# ai_blinkle_16.net
KiCad netlist of a schematic drawn in EAGLE
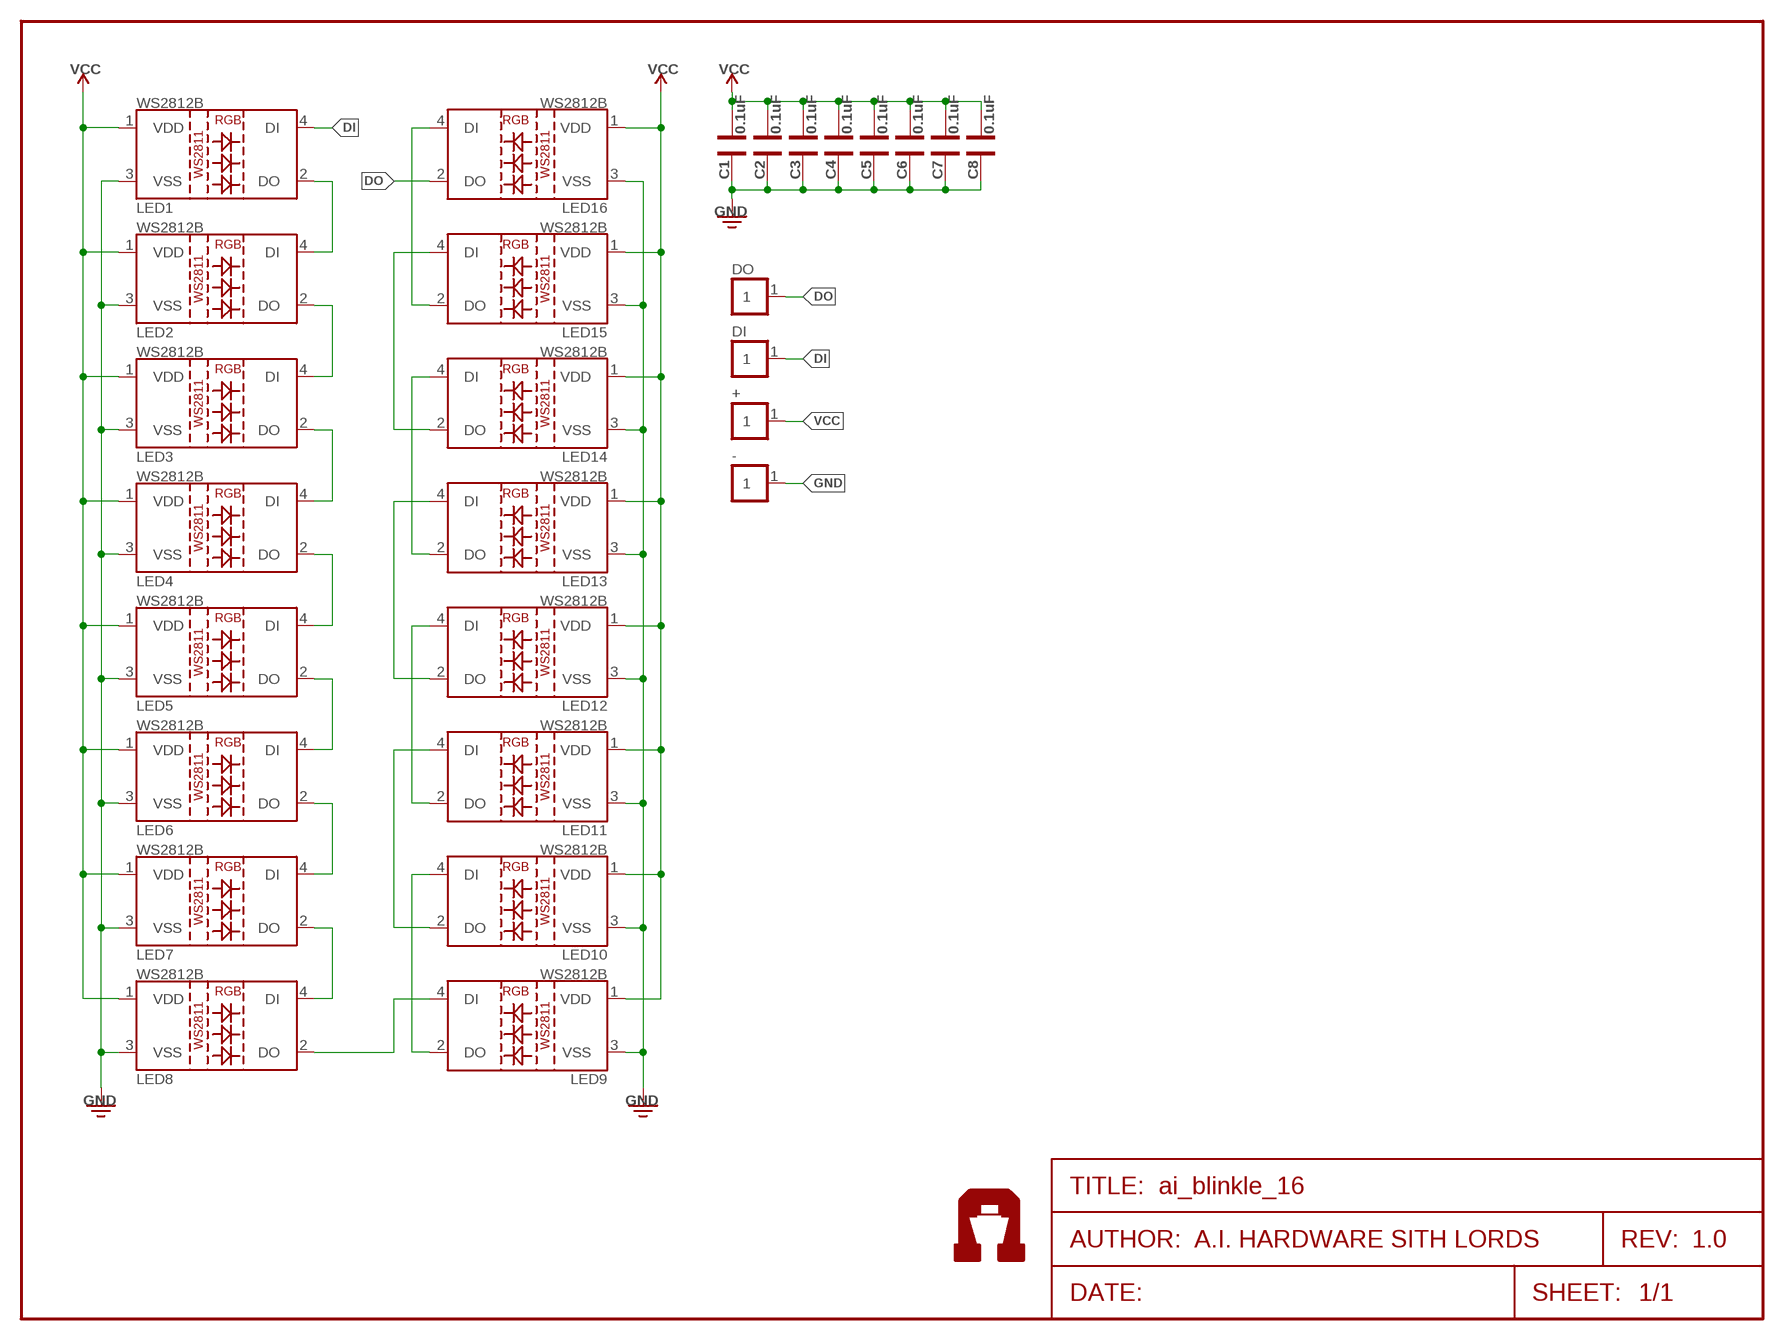
[diagram p0: schematic, sheet 1]

(export (version "E")
  (design (tool "Eeschema 10.0.6"))
  (components
    (comp (ref "+")
      (value "1X01-SM")
      (footprint "eagle-import:1X01-SM")
      (libsource (lib "eagle-import") (part "1X01-SM"))
    )
    (comp (ref "-")
      (value "1X01-SM")
      (footprint "eagle-import:1X01-SM")
      (libsource (lib "eagle-import") (part "1X01-SM"))
    )
    (comp (ref "C1")
      (value "0.1uF")
      (footprint "eagle-import:CAP-0402")
      (libsource (lib "eagle-import") (part "CAP0402"))
    )
    (comp (ref "C2")
      (value "0.1uF")
      (footprint "eagle-import:CAP-0402")
      (libsource (lib "eagle-import") (part "CAP0402"))
    )
    (comp (ref "C3")
      (value "0.1uF")
      (footprint "eagle-import:CAP-0402")
      (libsource (lib "eagle-import") (part "CAP0402"))
    )
    (comp (ref "C4")
      (value "0.1uF")
      (footprint "eagle-import:CAP-0402")
      (libsource (lib "eagle-import") (part "CAP0402"))
    )
    (comp (ref "C5")
      (value "0.1uF")
      (footprint "eagle-import:CAP-0402")
      (libsource (lib "eagle-import") (part "CAP0402"))
    )
    (comp (ref "C6")
      (value "0.1uF")
      (footprint "eagle-import:CAP-0402")
      (libsource (lib "eagle-import") (part "CAP0402"))
    )
    (comp (ref "C7")
      (value "0.1uF")
      (footprint "eagle-import:CAP-0402")
      (libsource (lib "eagle-import") (part "CAP0402"))
    )
    (comp (ref "C8")
      (value "0.1uF")
      (footprint "eagle-import:CAP-0402")
      (libsource (lib "eagle-import") (part "CAP0402"))
    )
    (comp (ref "DI")
      (value "1X01-SM")
      (footprint "eagle-import:1X01-SM")
      (libsource (lib "eagle-import") (part "1X01-SM"))
    )
    (comp (ref "DO")
      (value "1X01-SM")
      (footprint "eagle-import:1X01-SM")
      (libsource (lib "eagle-import") (part "1X01-SM"))
    )
    (comp (ref "LED1")
      (value "LED-WS2812B-SM")
      (footprint "eagle-import:LED-WS2812B-SM")
      (libsource (lib "eagle-import") (part "LED-WS2812B-SM"))
    )
    (comp (ref "LED2")
      (value "LED-WS2812B-SM")
      (footprint "eagle-import:LED-WS2812B-SM")
      (libsource (lib "eagle-import") (part "LED-WS2812B-SM"))
    )
    (comp (ref "LED3")
      (value "LED-WS2812B-SM")
      (footprint "eagle-import:LED-WS2812B-SM")
      (libsource (lib "eagle-import") (part "LED-WS2812B-SM"))
    )
    (comp (ref "LED4")
      (value "LED-WS2812B-SM")
      (footprint "eagle-import:LED-WS2812B-SM")
      (libsource (lib "eagle-import") (part "LED-WS2812B-SM"))
    )
    (comp (ref "LED5")
      (value "LED-WS2812B-SM")
      (footprint "eagle-import:LED-WS2812B-SM")
      (libsource (lib "eagle-import") (part "LED-WS2812B-SM"))
    )
    (comp (ref "LED6")
      (value "LED-WS2812B-SM")
      (footprint "eagle-import:LED-WS2812B-SM")
      (libsource (lib "eagle-import") (part "LED-WS2812B-SM"))
    )
    (comp (ref "LED7")
      (value "LED-WS2812B-SM")
      (footprint "eagle-import:LED-WS2812B-SM")
      (libsource (lib "eagle-import") (part "LED-WS2812B-SM"))
    )
    (comp (ref "LED8")
      (value "LED-WS2812B-SM")
      (footprint "eagle-import:LED-WS2812B-SM")
      (libsource (lib "eagle-import") (part "LED-WS2812B-SM"))
    )
    (comp (ref "LED9")
      (value "LED-WS2812B-SM")
      (footprint "eagle-import:LED-WS2812B-SM")
      (libsource (lib "eagle-import") (part "LED-WS2812B-SM"))
    )
    (comp (ref "LED10")
      (value "LED-WS2812B-SM")
      (footprint "eagle-import:LED-WS2812B-SM")
      (libsource (lib "eagle-import") (part "LED-WS2812B-SM"))
    )
    (comp (ref "LED11")
      (value "LED-WS2812B-SM")
      (footprint "eagle-import:LED-WS2812B-SM")
      (libsource (lib "eagle-import") (part "LED-WS2812B-SM"))
    )
    (comp (ref "LED12")
      (value "LED-WS2812B-SM")
      (footprint "eagle-import:LED-WS2812B-SM")
      (libsource (lib "eagle-import") (part "LED-WS2812B-SM"))
    )
    (comp (ref "LED13")
      (value "LED-WS2812B-SM")
      (footprint "eagle-import:LED-WS2812B-SM")
      (libsource (lib "eagle-import") (part "LED-WS2812B-SM"))
    )
    (comp (ref "LED14")
      (value "LED-WS2812B-SM")
      (footprint "eagle-import:LED-WS2812B-SM")
      (libsource (lib "eagle-import") (part "LED-WS2812B-SM"))
    )
    (comp (ref "LED15")
      (value "LED-WS2812B-SM")
      (footprint "eagle-import:LED-WS2812B-SM")
      (libsource (lib "eagle-import") (part "LED-WS2812B-SM"))
    )
    (comp (ref "LED16")
      (value "LED-WS2812B-SM")
      (footprint "eagle-import:LED-WS2812B-SM")
      (libsource (lib "eagle-import") (part "LED-WS2812B-SM"))
    )
    (comp (ref "LOGO")
      (value "AI-LOGOXS")
      (footprint "eagle-import:AI-LOGO-XS")
      (libsource (lib "eagle-import") (part "AI-LOGOXS"))
    )
  )
  (nets
    (net (code "1") (name "DI") (class "Default")
      (node (ref "DI") (pin "1") (pinfunction "1_1") (pintype "bidirectional"))
      (node (ref "LED1") (pin "4") (pinfunction "DI_4") (pintype "bidirectional"))
    )
    (net (code "2") (name "DO") (class "Default")
      (node (ref "DO") (pin "1") (pinfunction "1_1") (pintype "bidirectional"))
      (node (ref "LED16") (pin "2") (pinfunction "DO_2") (pintype "bidirectional"))
    )
    (net (code "3") (name "GND") (class "Default")
      (node (ref "-") (pin "1") (pinfunction "1_1") (pintype "bidirectional"))
      (node (ref "C1") (pin "2") (pinfunction "2_2") (pintype "passive"))
      (node (ref "C2") (pin "2") (pinfunction "2_2") (pintype "passive"))
      (node (ref "C3") (pin "2") (pinfunction "2_2") (pintype "passive"))
      (node (ref "C4") (pin "2") (pinfunction "2_2") (pintype "passive"))
      (node (ref "C5") (pin "2") (pinfunction "2_2") (pintype "passive"))
      (node (ref "C6") (pin "2") (pinfunction "2_2") (pintype "passive"))
      (node (ref "C7") (pin "2") (pinfunction "2_2") (pintype "passive"))
      (node (ref "C8") (pin "2") (pinfunction "2_2") (pintype "passive"))
      (node (ref "LED1") (pin "3") (pinfunction "VSS_3") (pintype "bidirectional"))
      (node (ref "LED10") (pin "3") (pinfunction "VSS_3") (pintype "bidirectional"))
      (node (ref "LED11") (pin "3") (pinfunction "VSS_3") (pintype "bidirectional"))
      (node (ref "LED12") (pin "3") (pinfunction "VSS_3") (pintype "bidirectional"))
      (node (ref "LED13") (pin "3") (pinfunction "VSS_3") (pintype "bidirectional"))
      (node (ref "LED14") (pin "3") (pinfunction "VSS_3") (pintype "bidirectional"))
      (node (ref "LED15") (pin "3") (pinfunction "VSS_3") (pintype "bidirectional"))
      (node (ref "LED16") (pin "3") (pinfunction "VSS_3") (pintype "bidirectional"))
      (node (ref "LED2") (pin "3") (pinfunction "VSS_3") (pintype "bidirectional"))
      (node (ref "LED3") (pin "3") (pinfunction "VSS_3") (pintype "bidirectional"))
      (node (ref "LED4") (pin "3") (pinfunction "VSS_3") (pintype "bidirectional"))
      (node (ref "LED5") (pin "3") (pinfunction "VSS_3") (pintype "bidirectional"))
      (node (ref "LED6") (pin "3") (pinfunction "VSS_3") (pintype "bidirectional"))
      (node (ref "LED7") (pin "3") (pinfunction "VSS_3") (pintype "bidirectional"))
      (node (ref "LED8") (pin "3") (pinfunction "VSS_3") (pintype "bidirectional"))
      (node (ref "LED9") (pin "3") (pinfunction "VSS_3") (pintype "bidirectional"))
    )
    (net (code "4") (name "Net-(LED1-DO)") (class "Default")
      (node (ref "LED1") (pin "2") (pinfunction "DO_2") (pintype "bidirectional"))
      (node (ref "LED2") (pin "4") (pinfunction "DI_4") (pintype "bidirectional"))
    )
    (net (code "5") (name "Net-(LED2-DO)") (class "Default")
      (node (ref "LED2") (pin "2") (pinfunction "DO_2") (pintype "bidirectional"))
      (node (ref "LED3") (pin "4") (pinfunction "DI_4") (pintype "bidirectional"))
    )
    (net (code "6") (name "Net-(LED3-DO)") (class "Default")
      (node (ref "LED3") (pin "2") (pinfunction "DO_2") (pintype "bidirectional"))
      (node (ref "LED4") (pin "4") (pinfunction "DI_4") (pintype "bidirectional"))
    )
    (net (code "7") (name "Net-(LED4-DO)") (class "Default")
      (node (ref "LED4") (pin "2") (pinfunction "DO_2") (pintype "bidirectional"))
      (node (ref "LED5") (pin "4") (pinfunction "DI_4") (pintype "bidirectional"))
    )
    (net (code "8") (name "Net-(LED5-DO)") (class "Default")
      (node (ref "LED5") (pin "2") (pinfunction "DO_2") (pintype "bidirectional"))
      (node (ref "LED6") (pin "4") (pinfunction "DI_4") (pintype "bidirectional"))
    )
    (net (code "9") (name "Net-(LED6-DO)") (class "Default")
      (node (ref "LED6") (pin "2") (pinfunction "DO_2") (pintype "bidirectional"))
      (node (ref "LED7") (pin "4") (pinfunction "DI_4") (pintype "bidirectional"))
    )
    (net (code "10") (name "Net-(LED7-DO)") (class "Default")
      (node (ref "LED7") (pin "2") (pinfunction "DO_2") (pintype "bidirectional"))
      (node (ref "LED8") (pin "4") (pinfunction "DI_4") (pintype "bidirectional"))
    )
    (net (code "11") (name "Net-(LED8-DO)") (class "Default")
      (node (ref "LED8") (pin "2") (pinfunction "DO_2") (pintype "bidirectional"))
      (node (ref "LED9") (pin "4") (pinfunction "DI_4") (pintype "bidirectional"))
    )
    (net (code "12") (name "Net-(LED10-DI)") (class "Default")
      (node (ref "LED10") (pin "4") (pinfunction "DI_4") (pintype "bidirectional"))
      (node (ref "LED9") (pin "2") (pinfunction "DO_2") (pintype "bidirectional"))
    )
    (net (code "13") (name "Net-(LED10-DO)") (class "Default")
      (node (ref "LED10") (pin "2") (pinfunction "DO_2") (pintype "bidirectional"))
      (node (ref "LED11") (pin "4") (pinfunction "DI_4") (pintype "bidirectional"))
    )
    (net (code "14") (name "Net-(LED11-DO)") (class "Default")
      (node (ref "LED11") (pin "2") (pinfunction "DO_2") (pintype "bidirectional"))
      (node (ref "LED12") (pin "4") (pinfunction "DI_4") (pintype "bidirectional"))
    )
    (net (code "15") (name "Net-(LED12-DO)") (class "Default")
      (node (ref "LED12") (pin "2") (pinfunction "DO_2") (pintype "bidirectional"))
      (node (ref "LED13") (pin "4") (pinfunction "DI_4") (pintype "bidirectional"))
    )
    (net (code "16") (name "Net-(LED13-DO)") (class "Default")
      (node (ref "LED13") (pin "2") (pinfunction "DO_2") (pintype "bidirectional"))
      (node (ref "LED14") (pin "4") (pinfunction "DI_4") (pintype "bidirectional"))
    )
    (net (code "17") (name "Net-(LED14-DO)") (class "Default")
      (node (ref "LED14") (pin "2") (pinfunction "DO_2") (pintype "bidirectional"))
      (node (ref "LED15") (pin "4") (pinfunction "DI_4") (pintype "bidirectional"))
    )
    (net (code "18") (name "Net-(LED15-DO)") (class "Default")
      (node (ref "LED15") (pin "2") (pinfunction "DO_2") (pintype "bidirectional"))
      (node (ref "LED16") (pin "4") (pinfunction "DI_4") (pintype "bidirectional"))
    )
    (net (code "19") (name "VCC") (class "Default")
      (node (ref "+") (pin "1") (pinfunction "1_1") (pintype "bidirectional"))
      (node (ref "C1") (pin "1") (pinfunction "1_1") (pintype "passive"))
      (node (ref "C2") (pin "1") (pinfunction "1_1") (pintype "passive"))
      (node (ref "C3") (pin "1") (pinfunction "1_1") (pintype "passive"))
      (node (ref "C4") (pin "1") (pinfunction "1_1") (pintype "passive"))
      (node (ref "C5") (pin "1") (pinfunction "1_1") (pintype "passive"))
      (node (ref "C6") (pin "1") (pinfunction "1_1") (pintype "passive"))
      (node (ref "C7") (pin "1") (pinfunction "1_1") (pintype "passive"))
      (node (ref "C8") (pin "1") (pinfunction "1_1") (pintype "passive"))
      (node (ref "LED1") (pin "1") (pinfunction "VDD_1") (pintype "bidirectional"))
      (node (ref "LED10") (pin "1") (pinfunction "VDD_1") (pintype "bidirectional"))
      (node (ref "LED11") (pin "1") (pinfunction "VDD_1") (pintype "bidirectional"))
      (node (ref "LED12") (pin "1") (pinfunction "VDD_1") (pintype "bidirectional"))
      (node (ref "LED13") (pin "1") (pinfunction "VDD_1") (pintype "bidirectional"))
      (node (ref "LED14") (pin "1") (pinfunction "VDD_1") (pintype "bidirectional"))
      (node (ref "LED15") (pin "1") (pinfunction "VDD_1") (pintype "bidirectional"))
      (node (ref "LED16") (pin "1") (pinfunction "VDD_1") (pintype "bidirectional"))
      (node (ref "LED2") (pin "1") (pinfunction "VDD_1") (pintype "bidirectional"))
      (node (ref "LED3") (pin "1") (pinfunction "VDD_1") (pintype "bidirectional"))
      (node (ref "LED4") (pin "1") (pinfunction "VDD_1") (pintype "bidirectional"))
      (node (ref "LED5") (pin "1") (pinfunction "VDD_1") (pintype "bidirectional"))
      (node (ref "LED6") (pin "1") (pinfunction "VDD_1") (pintype "bidirectional"))
      (node (ref "LED7") (pin "1") (pinfunction "VDD_1") (pintype "bidirectional"))
      (node (ref "LED8") (pin "1") (pinfunction "VDD_1") (pintype "bidirectional"))
      (node (ref "LED9") (pin "1") (pinfunction "VDD_1") (pintype "bidirectional"))
    )
  )
)
